# CONNECTOR_A.net
KiCad netlist of a schematic drawn in Altium Designer
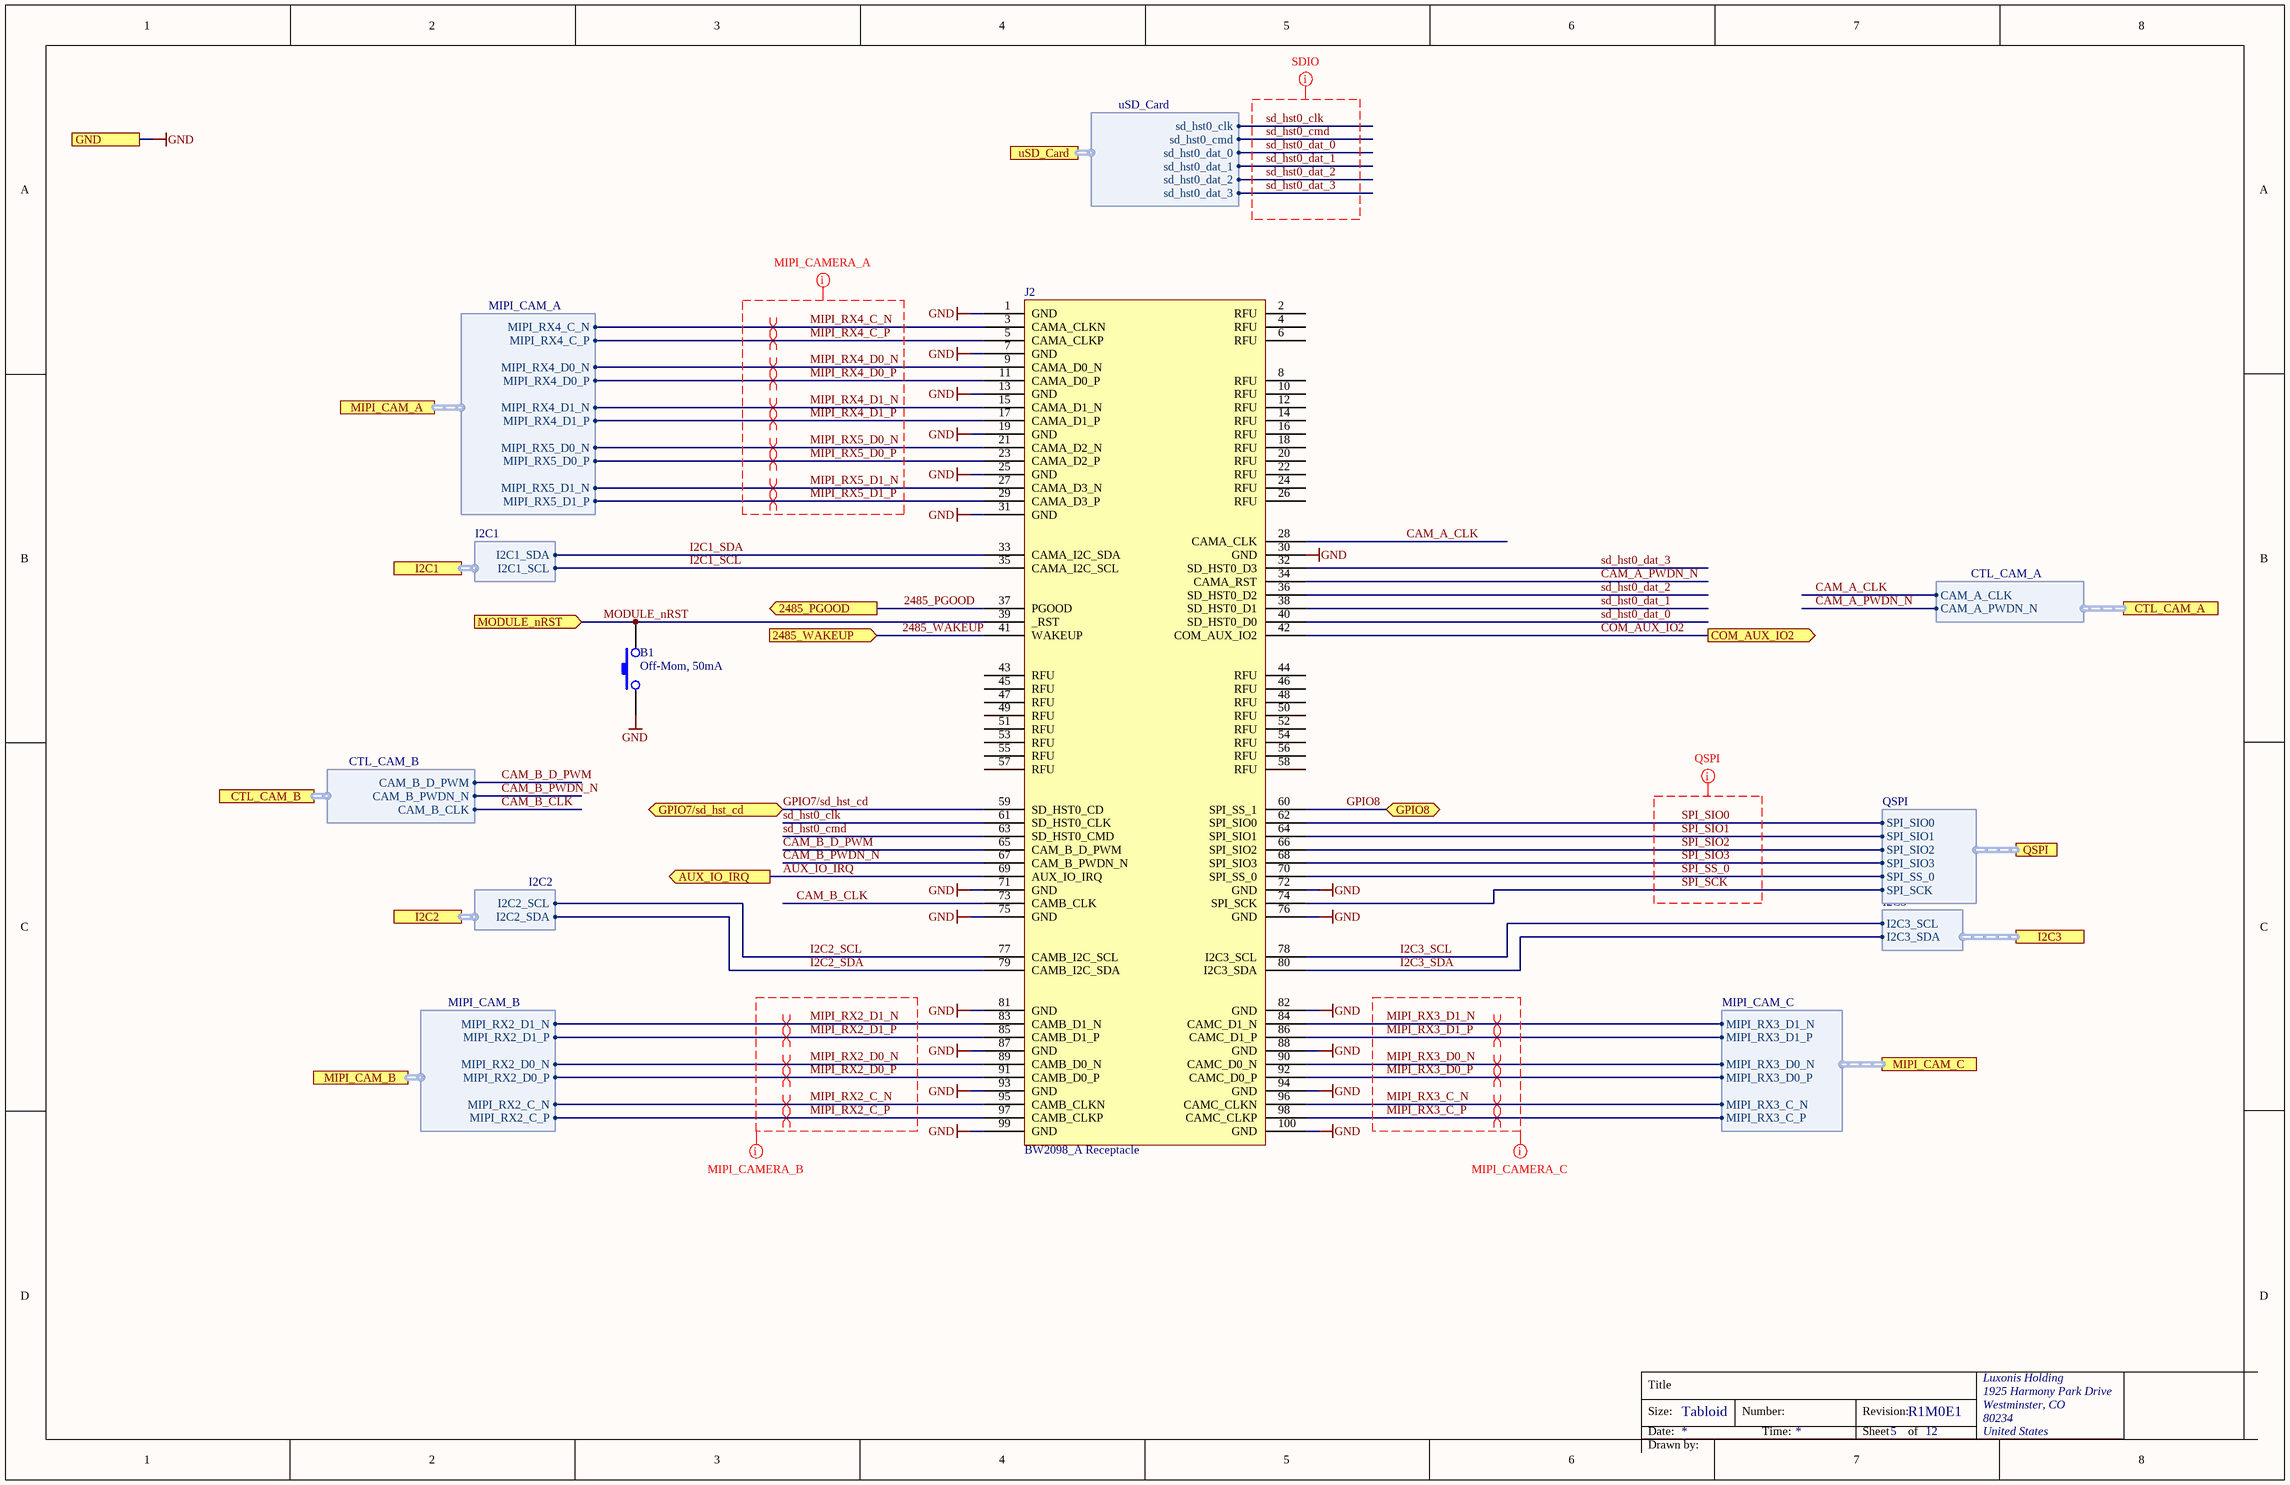
[diagram p0: CONNECTOR_A.SchDoc]

(export (version "E")
  (design (tool "Eeschema 10.0.6"))
  (components
    (comp (ref "B1")
      (value "Off-Mom, 50mA")
      (footprint "LuxonisMaster:DTSM-32N-V")
      (description "SWITCH TACTILE SMT 3.5mm * 6mm , brown 160gf")
      (libsource (lib "LuxonisMaster") (part "DTSM-32N-V"))
    )
    (comp (ref "J2")
      (value "BW2098_A Receptacle")
      (footprint "LuxonisMaster:DF40HC-3.0-100DS-0.4V_minpad")
      (description "CONN RCPT 100POS 0.4MM SMD GOLD BW2098_A Receptacle")
      (libsource (lib "BW2098POE") (part "DF40HC(3.0)-100DS-0.4V_BW2098_A"))
    )
  )
  (nets
    (net (code "11") (name "/2485_PGOOD") (class "Default")
      (node (ref "J2") (pin "37") (pinfunction "PGOOD_37") (pintype "passive"))
    )
    (net (code "12") (name "/2485_WAKEUP") (class "Default")
      (node (ref "J2") (pin "41") (pinfunction "WAKEUP_41") (pintype "passive"))
    )
    (net (code "13") (name "/AUX_IO_IRQ") (class "Default")
      (node (ref "J2") (pin "69") (pinfunction "AUX_IO_IRQ_69") (pintype "passive"))
    )
    (net (code "14") (name "/CAM_A_CLK") (class "Default")
      (node (ref "J2") (pin "28") (pinfunction "CAMA_CLK_28") (pintype "passive"))
    )
    (net (code "15") (name "/CAM_A_PWDN_N") (class "Default")
      (node (ref "J2") (pin "34") (pinfunction "CAMA_RST_34") (pintype "passive"))
    )
    (net (code "16") (name "/CAM_B_CLK") (class "Default")
      (node (ref "J2") (pin "73") (pinfunction "CAMB_CLK_73") (pintype "passive"))
    )
    (net (code "17") (name "/CAM_B_D_PWM") (class "Default")
      (node (ref "J2") (pin "65") (pinfunction "CAM_B_D_PWM_65") (pintype "passive"))
    )
    (net (code "18") (name "/CAM_B_PWDN_N") (class "Default")
      (node (ref "J2") (pin "67") (pinfunction "CAM_B_PWDN_N_67") (pintype "passive"))
    )
    (net (code "19") (name "/COM_AUX_IO2") (class "Default")
      (node (ref "J2") (pin "42") (pinfunction "COM_AUX_IO2_42") (pintype "passive"))
    )
    (net (code "20") (name "/GPIO7{slash}sd_hst_cd") (class "Default")
      (node (ref "J2") (pin "59") (pinfunction "SD_HST0_CD_59") (pintype "passive"))
    )
    (net (code "21") (name "/GPIO8") (class "Default")
      (node (ref "J2") (pin "60") (pinfunction "SPI_SS_1_60") (pintype "passive"))
    )
    (net (code "22") (name "/I2C1_SCL") (class "Default")
      (node (ref "J2") (pin "35") (pinfunction "CAMA_I2C_SCL_35") (pintype "passive"))
    )
    (net (code "23") (name "/I2C1_SDA") (class "Default")
      (node (ref "J2") (pin "33") (pinfunction "CAMA_I2C_SDA_33") (pintype "passive"))
    )
    (net (code "24") (name "/I2C2_SCL") (class "Default")
      (node (ref "J2") (pin "77") (pinfunction "CAMB_I2C_SCL_77") (pintype "passive"))
    )
    (net (code "25") (name "/I2C2_SDA") (class "Default")
      (node (ref "J2") (pin "79") (pinfunction "CAMB_I2C_SDA_79") (pintype "passive"))
    )
    (net (code "26") (name "/I2C3_SCL") (class "Default")
      (node (ref "J2") (pin "78") (pinfunction "I2C3_SCL_78") (pintype "passive"))
    )
    (net (code "27") (name "/I2C3_SDA") (class "Default")
      (node (ref "J2") (pin "80") (pinfunction "I2C3_SDA_80") (pintype "passive"))
    )
    (net (code "28") (name "/MIPI_RX2_C_N") (class "Default")
      (node (ref "J2") (pin "95") (pinfunction "CAMB_CLKN_95") (pintype "passive"))
    )
    (net (code "29") (name "/MIPI_RX2_C_P") (class "Default")
      (node (ref "J2") (pin "97") (pinfunction "CAMB_CLKP_97") (pintype "passive"))
    )
    (net (code "30") (name "/MIPI_RX2_D0_N") (class "Default")
      (node (ref "J2") (pin "89") (pinfunction "CAMB_D0_N_89") (pintype "passive"))
    )
    (net (code "31") (name "/MIPI_RX2_D0_P") (class "Default")
      (node (ref "J2") (pin "91") (pinfunction "CAMB_D0_P_91") (pintype "passive"))
    )
    (net (code "32") (name "/MIPI_RX2_D1_N") (class "Default")
      (node (ref "J2") (pin "83") (pinfunction "CAMB_D1_N_83") (pintype "passive"))
    )
    (net (code "33") (name "/MIPI_RX2_D1_P") (class "Default")
      (node (ref "J2") (pin "85") (pinfunction "CAMB_D1_P_85") (pintype "passive"))
    )
    (net (code "34") (name "/MIPI_RX3_C_N") (class "Default")
      (node (ref "J2") (pin "96") (pinfunction "CAMC_CLKN_96") (pintype "passive"))
    )
    (net (code "35") (name "/MIPI_RX3_C_P") (class "Default")
      (node (ref "J2") (pin "98") (pinfunction "CAMC_CLKP_98") (pintype "passive"))
    )
    (net (code "36") (name "/MIPI_RX3_D0_N") (class "Default")
      (node (ref "J2") (pin "90") (pinfunction "CAMC_D0_N_90") (pintype "passive"))
    )
    (net (code "37") (name "/MIPI_RX3_D0_P") (class "Default")
      (node (ref "J2") (pin "92") (pinfunction "CAMC_D0_P_92") (pintype "passive"))
    )
    (net (code "38") (name "/MIPI_RX3_D1_N") (class "Default")
      (node (ref "J2") (pin "84") (pinfunction "CAMC_D1_N_84") (pintype "passive"))
    )
    (net (code "39") (name "/MIPI_RX3_D1_P") (class "Default")
      (node (ref "J2") (pin "86") (pinfunction "CAMC_D1_P_86") (pintype "passive"))
    )
    (net (code "40") (name "/MIPI_RX4_C_N") (class "Default")
      (node (ref "J2") (pin "3") (pinfunction "CAMA_CLKN_3") (pintype "passive"))
    )
    (net (code "41") (name "/MIPI_RX4_C_P") (class "Default")
      (node (ref "J2") (pin "5") (pinfunction "CAMA_CLKP_5") (pintype "passive"))
    )
    (net (code "42") (name "/MIPI_RX4_D0_N") (class "Default")
      (node (ref "J2") (pin "9") (pinfunction "CAMA_D0_N_9") (pintype "passive"))
    )
    (net (code "43") (name "/MIPI_RX4_D0_P") (class "Default")
      (node (ref "J2") (pin "11") (pinfunction "CAMA_D0_P_11") (pintype "passive"))
    )
    (net (code "44") (name "/MIPI_RX4_D1_N") (class "Default")
      (node (ref "J2") (pin "15") (pinfunction "CAMA_D1_N_15") (pintype "passive"))
    )
    (net (code "45") (name "/MIPI_RX4_D1_P") (class "Default")
      (node (ref "J2") (pin "17") (pinfunction "CAMA_D1_P_17") (pintype "passive"))
    )
    (net (code "46") (name "/MIPI_RX5_D0_N") (class "Default")
      (node (ref "J2") (pin "21") (pinfunction "CAMA_D2_N_21") (pintype "passive"))
    )
    (net (code "47") (name "/MIPI_RX5_D0_P") (class "Default")
      (node (ref "J2") (pin "23") (pinfunction "CAMA_D2_P_23") (pintype "passive"))
    )
    (net (code "48") (name "/MIPI_RX5_D1_N") (class "Default")
      (node (ref "J2") (pin "27") (pinfunction "CAMA_D3_N_27") (pintype "passive"))
    )
    (net (code "49") (name "/MIPI_RX5_D1_P") (class "Default")
      (node (ref "J2") (pin "29") (pinfunction "CAMA_D3_P_29") (pintype "passive"))
    )
    (net (code "50") (name "/MODULE_nRST") (class "Default")
      (node (ref "B1") (pin "2") (pinfunction "2_2") (pintype "passive"))
      (node (ref "J2") (pin "39") (pinfunction "_RST_39") (pintype "passive"))
    )
    (net (code "51") (name "/SPI_SCK") (class "Default")
      (node (ref "J2") (pin "74") (pinfunction "SPI_SCK_74") (pintype "passive"))
    )
    (net (code "52") (name "/SPI_SIO0") (class "Default")
      (node (ref "J2") (pin "62") (pinfunction "SPI_SIO0_62") (pintype "passive"))
    )
    (net (code "53") (name "/SPI_SIO1") (class "Default")
      (node (ref "J2") (pin "64") (pinfunction "SPI_SIO1_64") (pintype "passive"))
    )
    (net (code "54") (name "/SPI_SIO2") (class "Default")
      (node (ref "J2") (pin "66") (pinfunction "SPI_SIO2_66") (pintype "passive"))
    )
    (net (code "55") (name "/SPI_SIO3") (class "Default")
      (node (ref "J2") (pin "68") (pinfunction "SPI_SIO3_68") (pintype "passive"))
    )
    (net (code "56") (name "/SPI_SS_0") (class "Default")
      (node (ref "J2") (pin "70") (pinfunction "SPI_SS_0_70") (pintype "passive"))
    )
    (net (code "57") (name "/sd_hst0_clk") (class "Default")
      (node (ref "J2") (pin "61") (pinfunction "SD_HST0_CLK_61") (pintype "passive"))
    )
    (net (code "58") (name "/sd_hst0_cmd") (class "Default")
      (node (ref "J2") (pin "63") (pinfunction "SD_HST0_CMD_63") (pintype "passive"))
    )
    (net (code "59") (name "/sd_hst0_dat_0") (class "Default")
      (node (ref "J2") (pin "40") (pinfunction "SD_HST0_D0_40") (pintype "passive"))
    )
    (net (code "60") (name "/sd_hst0_dat_1") (class "Default")
      (node (ref "J2") (pin "38") (pinfunction "SD_HST0_D1_38") (pintype "passive"))
    )
    (net (code "61") (name "/sd_hst0_dat_2") (class "Default")
      (node (ref "J2") (pin "36") (pinfunction "SD_HST0_D2_36") (pintype "passive"))
    )
    (net (code "62") (name "/sd_hst0_dat_3") (class "Default")
      (node (ref "J2") (pin "32") (pinfunction "SD_HST0_D3_32") (pintype "passive"))
    )
    (net (code "73") (name "GND") (class "Default")
      (node (ref "B1") (pin "1") (pinfunction "1_1") (pintype "passive"))
      (node (ref "J2") (pin "1") (pinfunction "GND_1") (pintype "passive"))
      (node (ref "J2") (pin "100") (pinfunction "GND_100") (pintype "passive"))
      (node (ref "J2") (pin "13") (pinfunction "GND_13") (pintype "passive"))
      (node (ref "J2") (pin "19") (pinfunction "GND_19") (pintype "passive"))
      (node (ref "J2") (pin "25") (pinfunction "GND_25") (pintype "passive"))
      (node (ref "J2") (pin "30") (pinfunction "GND_30") (pintype "passive"))
      (node (ref "J2") (pin "31") (pinfunction "GND_31") (pintype "passive"))
      (node (ref "J2") (pin "7") (pinfunction "GND_7") (pintype "passive"))
      (node (ref "J2") (pin "71") (pinfunction "GND_71") (pintype "passive"))
      (node (ref "J2") (pin "72") (pinfunction "GND_72") (pintype "passive"))
      (node (ref "J2") (pin "75") (pinfunction "GND_75") (pintype "passive"))
      (node (ref "J2") (pin "76") (pinfunction "GND_76") (pintype "passive"))
      (node (ref "J2") (pin "81") (pinfunction "GND_81") (pintype "passive"))
      (node (ref "J2") (pin "82") (pinfunction "GND_82") (pintype "passive"))
      (node (ref "J2") (pin "87") (pinfunction "GND_87") (pintype "passive"))
      (node (ref "J2") (pin "88") (pinfunction "GND_88") (pintype "passive"))
      (node (ref "J2") (pin "93") (pinfunction "GND_93") (pintype "passive"))
      (node (ref "J2") (pin "94") (pinfunction "GND_94") (pintype "passive"))
      (node (ref "J2") (pin "99") (pinfunction "GND_99") (pintype "passive"))
    )
    (net (code "74") (name "unconnected-(J2-RFU-Pad2)") (class "Default")
      (node (ref "J2") (pin "2") (pinfunction "RFU_2") (pintype "passive"))
    )
    (net (code "75") (name "unconnected-(J2-RFU-Pad4)") (class "Default")
      (node (ref "J2") (pin "4") (pinfunction "RFU_4") (pintype "passive"))
    )
    (net (code "76") (name "unconnected-(J2-RFU-Pad6)") (class "Default")
      (node (ref "J2") (pin "6") (pinfunction "RFU_6") (pintype "passive"))
    )
    (net (code "77") (name "unconnected-(J2-RFU-Pad8)") (class "Default")
      (node (ref "J2") (pin "8") (pinfunction "RFU_8") (pintype "passive"))
    )
    (net (code "78") (name "unconnected-(J2-RFU-Pad10)") (class "Default")
      (node (ref "J2") (pin "10") (pinfunction "RFU_10") (pintype "passive"))
    )
    (net (code "79") (name "unconnected-(J2-RFU-Pad12)") (class "Default")
      (node (ref "J2") (pin "12") (pinfunction "RFU_12") (pintype "passive"))
    )
    (net (code "80") (name "unconnected-(J2-RFU-Pad14)") (class "Default")
      (node (ref "J2") (pin "14") (pinfunction "RFU_14") (pintype "passive"))
    )
    (net (code "81") (name "unconnected-(J2-RFU-Pad16)") (class "Default")
      (node (ref "J2") (pin "16") (pinfunction "RFU_16") (pintype "passive"))
    )
    (net (code "82") (name "unconnected-(J2-RFU-Pad18)") (class "Default")
      (node (ref "J2") (pin "18") (pinfunction "RFU_18") (pintype "passive"))
    )
    (net (code "83") (name "unconnected-(J2-RFU-Pad20)") (class "Default")
      (node (ref "J2") (pin "20") (pinfunction "RFU_20") (pintype "passive"))
    )
    (net (code "84") (name "unconnected-(J2-RFU-Pad22)") (class "Default")
      (node (ref "J2") (pin "22") (pinfunction "RFU_22") (pintype "passive"))
    )
    (net (code "85") (name "unconnected-(J2-RFU-Pad24)") (class "Default")
      (node (ref "J2") (pin "24") (pinfunction "RFU_24") (pintype "passive"))
    )
    (net (code "86") (name "unconnected-(J2-RFU-Pad26)") (class "Default")
      (node (ref "J2") (pin "26") (pinfunction "RFU_26") (pintype "passive"))
    )
    (net (code "87") (name "unconnected-(J2-RFU-Pad43)") (class "Default")
      (node (ref "J2") (pin "43") (pinfunction "RFU_43") (pintype "passive"))
    )
    (net (code "88") (name "unconnected-(J2-RFU-Pad44)") (class "Default")
      (node (ref "J2") (pin "44") (pinfunction "RFU_44") (pintype "passive"))
    )
    (net (code "89") (name "unconnected-(J2-RFU-Pad45)") (class "Default")
      (node (ref "J2") (pin "45") (pinfunction "RFU_45") (pintype "passive"))
    )
    (net (code "90") (name "unconnected-(J2-RFU-Pad46)") (class "Default")
      (node (ref "J2") (pin "46") (pinfunction "RFU_46") (pintype "passive"))
    )
    (net (code "91") (name "unconnected-(J2-RFU-Pad47)") (class "Default")
      (node (ref "J2") (pin "47") (pinfunction "RFU_47") (pintype "passive"))
    )
    (net (code "92") (name "unconnected-(J2-RFU-Pad48)") (class "Default")
      (node (ref "J2") (pin "48") (pinfunction "RFU_48") (pintype "passive"))
    )
    (net (code "93") (name "unconnected-(J2-RFU-Pad49)") (class "Default")
      (node (ref "J2") (pin "49") (pinfunction "RFU_49") (pintype "passive"))
    )
    (net (code "94") (name "unconnected-(J2-RFU-Pad50)") (class "Default")
      (node (ref "J2") (pin "50") (pinfunction "RFU_50") (pintype "passive"))
    )
    (net (code "95") (name "unconnected-(J2-RFU-Pad51)") (class "Default")
      (node (ref "J2") (pin "51") (pinfunction "RFU_51") (pintype "passive"))
    )
    (net (code "96") (name "unconnected-(J2-RFU-Pad52)") (class "Default")
      (node (ref "J2") (pin "52") (pinfunction "RFU_52") (pintype "passive"))
    )
    (net (code "97") (name "unconnected-(J2-RFU-Pad53)") (class "Default")
      (node (ref "J2") (pin "53") (pinfunction "RFU_53") (pintype "passive"))
    )
    (net (code "98") (name "unconnected-(J2-RFU-Pad54)") (class "Default")
      (node (ref "J2") (pin "54") (pinfunction "RFU_54") (pintype "passive"))
    )
    (net (code "99") (name "unconnected-(J2-RFU-Pad55)") (class "Default")
      (node (ref "J2") (pin "55") (pinfunction "RFU_55") (pintype "passive"))
    )
    (net (code "100") (name "unconnected-(J2-RFU-Pad56)") (class "Default")
      (node (ref "J2") (pin "56") (pinfunction "RFU_56") (pintype "passive"))
    )
    (net (code "101") (name "unconnected-(J2-RFU-Pad57)") (class "Default")
      (node (ref "J2") (pin "57") (pinfunction "RFU_57") (pintype "passive"))
    )
    (net (code "102") (name "unconnected-(J2-RFU-Pad58)") (class "Default")
      (node (ref "J2") (pin "58") (pinfunction "RFU_58") (pintype "passive"))
    )
  )
)
